# main.net
KiCad netlist of a schematic drawn in Altium Designer
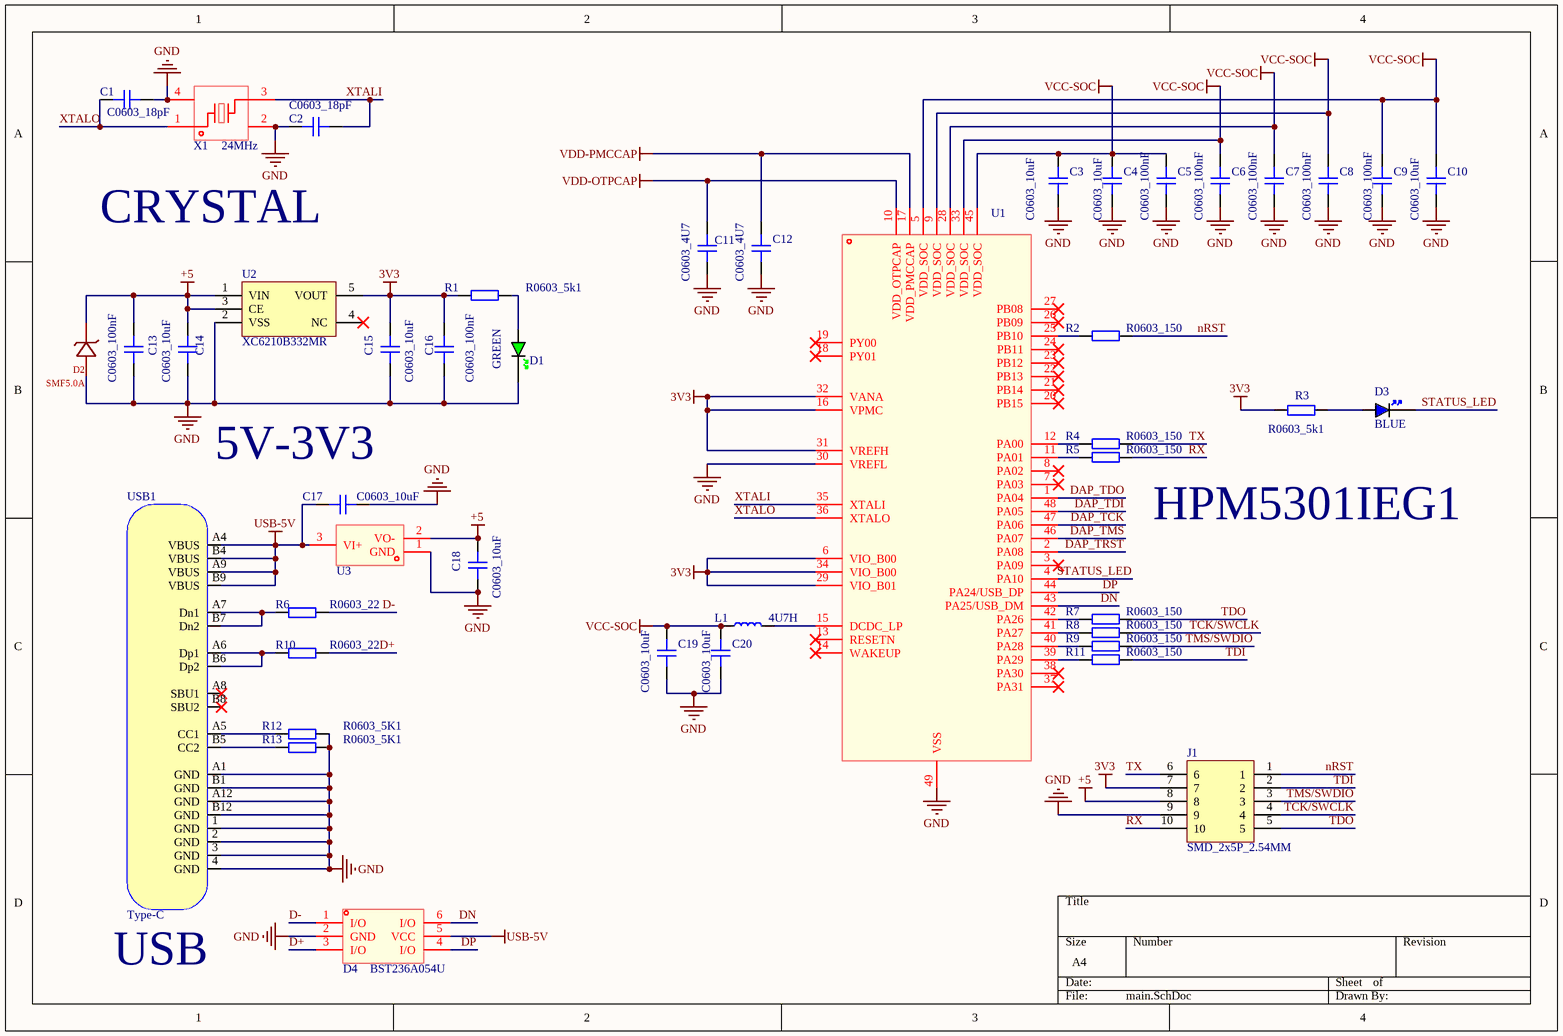
[diagram p0: main.SchDoc]

(export (version "E")
  (design (tool "Eeschema 10.0.6"))
  (components
    (comp (ref "C1")
      (value "C0603_18pF")
      (footprint "CAP_0603")
      (description "Capacitor SMD 0603")
      (libsource (lib "MyLib") (part "CAP_0603"))
    )
    (comp (ref "C2")
      (value "C0603_18pF")
      (footprint "CAP_0603")
      (description "Capacitor SMD 0603")
      (libsource (lib "MyLib") (part "CAP_0603"))
    )
    (comp (ref "C3")
      (value "C0603_10uF")
      (footprint "CAP_0603")
      (description "Capacitor SMD 0603")
      (libsource (lib "MyLib") (part "CAP_0603"))
    )
    (comp (ref "C4")
      (value "C0603_10uF")
      (footprint "CAP_0603")
      (description "Capacitor SMD 0603")
      (libsource (lib "MyLib") (part "CAP_0603"))
    )
    (comp (ref "C5")
      (value "C0603_100nF")
      (footprint "CAP_0603")
      (description "Capacitor SMD 0603")
      (libsource (lib "MyLib") (part "CAP_0603"))
    )
    (comp (ref "C6")
      (value "C0603_100nF")
      (footprint "CAP_0603")
      (description "Capacitor SMD 0603")
      (libsource (lib "MyLib") (part "CAP_0603"))
    )
    (comp (ref "C7")
      (value "C0603_100nF")
      (footprint "CAP_0603")
      (description "Capacitor SMD 0603")
      (libsource (lib "MyLib") (part "CAP_0603"))
    )
    (comp (ref "C8")
      (value "C0603_100nF")
      (footprint "CAP_0603")
      (description "Capacitor SMD 0603")
      (libsource (lib "MyLib") (part "CAP_0603"))
    )
    (comp (ref "C9")
      (value "C0603_100nF")
      (footprint "CAP_0603")
      (description "Capacitor SMD 0603")
      (libsource (lib "MyLib") (part "CAP_0603"))
    )
    (comp (ref "C10")
      (value "C0603_10uF")
      (footprint "CAP_0603")
      (description "Capacitor SMD 0603")
      (libsource (lib "MyLib") (part "CAP_0603"))
    )
    (comp (ref "C11")
      (value "C0603_4U7")
      (footprint "CAP_0603")
      (description "Capacitor SMD 0603")
      (libsource (lib "MyLib") (part "CAP_0603"))
    )
    (comp (ref "C12")
      (value "C0603_4U7")
      (footprint "CAP_0603")
      (description "Capacitor SMD 0603")
      (libsource (lib "MyLib") (part "CAP_0603"))
    )
    (comp (ref "C13")
      (value "C0603_100nF")
      (footprint "CAP_0603")
      (description "Capacitor SMD 0603")
      (libsource (lib "MyLib") (part "CAP_0603"))
    )
    (comp (ref "C14")
      (value "C0603_10uF")
      (footprint "CAP_0603")
      (description "Capacitor SMD 0603")
      (libsource (lib "MyLib") (part "CAP_0603"))
    )
    (comp (ref "C15")
      (value "C0603_10uF")
      (footprint "CAP_0603")
      (description "Capacitor SMD 0603")
      (libsource (lib "MyLib") (part "CAP_0603"))
    )
    (comp (ref "C16")
      (value "C0603_100nF")
      (footprint "CAP_0603")
      (description "Capacitor SMD 0603")
      (libsource (lib "MyLib") (part "CAP_0603"))
    )
    (comp (ref "C17")
      (value "C0603_10uF")
      (footprint "CAP_0603")
      (description "Capacitor SMD 0603")
      (libsource (lib "MyLib") (part "CAP_0603"))
    )
    (comp (ref "C18")
      (value "C0603_10uF")
      (footprint "CAP_0603")
      (description "Capacitor SMD 0603")
      (libsource (lib "MyLib") (part "CAP_0603"))
    )
    (comp (ref "C19")
      (value "C0603_10uF")
      (footprint "CAP_0603")
      (description "Capacitor SMD 0603")
      (libsource (lib "MyLib") (part "CAP_0603"))
    )
    (comp (ref "C20")
      (value "C0603_10uF")
      (footprint "CAP_0603")
      (description "Capacitor SMD 0603")
      (libsource (lib "MyLib") (part "CAP_0603"))
    )
    (comp (ref "D1")
      (value "GREEN")
      (footprint "LED_0805_GREEN")
      (description "LED 0805 GREEN SMD")
      (libsource (lib "MyLib") (part "LED_0805_GREEN"))
    )
    (comp (ref "D2")
      (value "SMF5.0A")
      (footprint "SOD-123FL_L2.7-W1.8-LS3.8-RD")
      (description "极性:单向;反向截止电压(Vrwm):5V;钳位电压:9.2V;峰值脉冲电流(Ipp):21.7A@10/1000us;峰值脉冲功率(Ppp):200W@10/1000us;击穿电压:7V;")
      (fields (field (name "MANUFACTURER") "R+O(宏嘉诚)"))
      (libsource (lib "MyLib") (part "SMF5.0A_C19077497"))
    )
    (comp (ref "D3")
      (value "BLUE")
      (footprint "LED_0805_BLUE")
      (description "LED 0805 BLUE SMD")
      (libsource (lib "MyLib") (part "LED_0805_BLUE"))
    )
    (comp (ref "D4")
      (value "BST236A054U")
      (footprint "SOT-23-6_L2.9-W1.6-P0.95-LS2.9-BL")
      (description "极性:-;反向截止电压(Vrwm):5V;钳位电压:13V;峰值脉冲电流(Ipp):3.5A;峰值脉冲功率(Ppp):45W@8/20us;击穿电压:6V;")
      (fields (field (name "MANUFACTURER") "BORN(伯恩半导体)"))
      (libsource (lib "MyLib") (part "BST236A054U"))
    )
    (comp (ref "J1")
      (value "SMD_2x5P_2.54MM")
      (footprint "SMD_2x5P_2.54MM")
      (libsource (lib "MyLib") (part "SMD_2x5P_2.54MM"))
    )
    (comp (ref "L1")
      (value "4U7H")
      (footprint "IND_1008")
      (description "Inductor SMD 1008")
      (libsource (lib "MyLib") (part "IND_1008"))
    )
    (comp (ref "R1")
      (value "R0603_5k1")
      (footprint "RES_0603")
      (description "Resistor SMD 0603")
      (libsource (lib "MyLib") (part "RES_0603"))
    )
    (comp (ref "R2")
      (value "R0603_150")
      (footprint "RES_0603")
      (description "Resistor SMD 0603")
      (libsource (lib "MyLib") (part "RES_0603"))
    )
    (comp (ref "R3")
      (value "R0603_5k1")
      (footprint "RES_0603")
      (description "Resistor SMD 0603")
      (libsource (lib "MyLib") (part "RES_0603"))
    )
    (comp (ref "R4")
      (value "R0603_150")
      (footprint "RES_0603")
      (description "Resistor SMD 0603")
      (libsource (lib "MyLib") (part "RES_0603"))
    )
    (comp (ref "R5")
      (value "R0603_150")
      (footprint "RES_0603")
      (description "Resistor SMD 0603")
      (libsource (lib "MyLib") (part "RES_0603"))
    )
    (comp (ref "R6")
      (value "R0603_22")
      (footprint "RES_0603")
      (description "Resistor SMD 0603")
      (libsource (lib "MyLib") (part "RES_0603"))
    )
    (comp (ref "R7")
      (value "R0603_150")
      (footprint "RES_0603")
      (description "Resistor SMD 0603")
      (libsource (lib "MyLib") (part "RES_0603"))
    )
    (comp (ref "R8")
      (value "R0603_150")
      (footprint "RES_0603")
      (description "Resistor SMD 0603")
      (libsource (lib "MyLib") (part "RES_0603"))
    )
    (comp (ref "R9")
      (value "R0603_150")
      (footprint "RES_0603")
      (description "Resistor SMD 0603")
      (libsource (lib "MyLib") (part "RES_0603"))
    )
    (comp (ref "R10")
      (value "R0603_22")
      (footprint "RES_0603")
      (description "Resistor SMD 0603")
      (libsource (lib "MyLib") (part "RES_0603"))
    )
    (comp (ref "R11")
      (value "R0603_150")
      (footprint "RES_0603")
      (description "Resistor SMD 0603")
      (libsource (lib "MyLib") (part "RES_0603"))
    )
    (comp (ref "R12")
      (value "R0603_5K1")
      (footprint "RES_0603")
      (description "Resistor SMD 0603")
      (libsource (lib "MyLib") (part "RES_0603"))
    )
    (comp (ref "R13")
      (value "R0603_5K1")
      (footprint "RES_0603")
      (description "Resistor SMD 0603")
      (libsource (lib "MyLib") (part "RES_0603"))
    )
    (comp (ref "U1")
      (value "HPM5301IEG1")
      (footprint "QFN-48_L6.0-W6.0-P0.40-TL-EP4.2")
      (fields (field (name "MANUFACTURER") "HPMICRO(先楫半导体)"))
      (libsource (lib "MyLib") (part "HPM5301IEG1_C49451864"))
    )
    (comp (ref "U2")
      (value "XC6210B332MR")
      (footprint "SOT-23-5")
      (description "LDO 3V3@700mA")
      (libsource (lib "MyLib") (part "XC6210B332MR"))
    )
    (comp (ref "U3")
      (value "CH213K")
      (footprint "SOT-23-3_L2.9-W1.6-P1.90-LS2.8-BR")
      (fields (field (name "MANUFACTURER") "WCH(南京沁恒)"))
      (libsource (lib "CHIPS") (part "CH213K"))
    )
    (comp (ref "USB1")
      (value "Type-C")
      (footprint "TYPE-C_16P")
      (description "USB-Type-C_16P")
      (libsource (lib "MyLib") (part "USB-Type-C"))
    )
    (comp (ref "X1")
      (value "24MHz")
      (footprint "CRYSTAL-SMD_4P-L2.5-W2.0-BL-A")
      (description "晶振类型:贴片晶振;频率:24MHz;常温频差:±10ppm;负载电容:18pF;频率稳定度:±10ppm;")
      (fields
        (field (name "MANUFACTURER") "HCI(杭晶)")
        (field (name "MANUFACTURER PART") "XC22M4-32.000-F08NNHP")
      )
      (libsource (lib "MyLib") (part "XTAL_2520_24MHz"))
    )
  )
  (nets
    (net (code "1") (name "+5") (class "Default")
      (node (ref "C13") (pin "1") (pinfunction "1_1") (pintype "passive"))
      (node (ref "C14") (pin "2") (pinfunction "2_2") (pintype "passive"))
      (node (ref "C18") (pin "2") (pinfunction "2_2") (pintype "passive"))
      (node (ref "D2") (pin "1") (pinfunction "K_1") (pintype "passive"))
      (node (ref "J1") (pin "8") (pinfunction "8_8") (pintype "passive"))
      (node (ref "U2") (pin "1") (pinfunction "VIN_1") (pintype "passive"))
      (node (ref "U2") (pin "3") (pinfunction "CE_3") (pintype "passive"))
      (node (ref "U3") (pin "2") (pinfunction "VO-_2") (pintype "passive"))
    )
    (net (code "2") (name "/D+") (class "Default")
      (node (ref "D4") (pin "3") (pinfunction "I/O_3") (pintype "passive"))
      (node (ref "R10") (pin "2") (pinfunction "2_2") (pintype "passive"))
    )
    (net (code "3") (name "/D-") (class "Default")
      (node (ref "D4") (pin "1") (pinfunction "I/O_1") (pintype "passive"))
      (node (ref "R6") (pin "2") (pinfunction "2_2") (pintype "passive"))
    )
    (net (code "4") (name "/DAP_TCK") (class "Default")
      (node (ref "U1") (pin "47") (pinfunction "PA06_47") (pintype "passive"))
    )
    (net (code "5") (name "/DAP_TDI") (class "Default")
      (node (ref "U1") (pin "48") (pinfunction "PA05_48") (pintype "passive"))
    )
    (net (code "6") (name "/DAP_TDO") (class "Default")
      (node (ref "U1") (pin "1") (pinfunction "PA04_1") (pintype "passive"))
    )
    (net (code "7") (name "/DAP_TMS") (class "Default")
      (node (ref "U1") (pin "46") (pinfunction "PA07_46") (pintype "passive"))
    )
    (net (code "8") (name "/DAP_TRST") (class "Default")
      (node (ref "U1") (pin "2") (pinfunction "PA08_2") (pintype "passive"))
    )
    (net (code "9") (name "/DN") (class "Default")
      (node (ref "D4") (pin "6") (pinfunction "I/O_6") (pintype "passive"))
      (node (ref "U1") (pin "43") (pinfunction "PA25/USB_DM_43") (pintype "passive"))
    )
    (net (code "10") (name "/DP") (class "Default")
      (node (ref "D4") (pin "4") (pinfunction "I/O_4") (pintype "passive"))
      (node (ref "U1") (pin "44") (pinfunction "PA24/USB_DP_44") (pintype "passive"))
    )
    (net (code "11") (name "/RX") (class "Default")
      (node (ref "J1") (pin "10") (pinfunction "10_10") (pintype "passive"))
      (node (ref "R5") (pin "2") (pinfunction "2_2") (pintype "passive"))
    )
    (net (code "12") (name "/STATUS_LED") (class "Default")
      (node (ref "D3") (pin "K") (pinfunction "K_K") (pintype "passive"))
      (node (ref "U1") (pin "4") (pinfunction "PA10_4") (pintype "passive"))
    )
    (net (code "13") (name "/TCK{slash}SWCLK") (class "Default")
      (node (ref "J1") (pin "4") (pinfunction "4_4") (pintype "passive"))
      (node (ref "R8") (pin "2") (pinfunction "2_2") (pintype "passive"))
    )
    (net (code "14") (name "/TDI") (class "Default")
      (node (ref "J1") (pin "2") (pinfunction "2_2") (pintype "passive"))
      (node (ref "R11") (pin "2") (pinfunction "2_2") (pintype "passive"))
    )
    (net (code "15") (name "/TDO") (class "Default")
      (node (ref "J1") (pin "5") (pinfunction "5_5") (pintype "passive"))
      (node (ref "R7") (pin "2") (pinfunction "2_2") (pintype "passive"))
    )
    (net (code "16") (name "/TMS{slash}SWDIO") (class "Default")
      (node (ref "J1") (pin "3") (pinfunction "3_3") (pintype "passive"))
      (node (ref "R9") (pin "2") (pinfunction "2_2") (pintype "passive"))
    )
    (net (code "17") (name "/TX") (class "Default")
      (node (ref "J1") (pin "6") (pinfunction "6_6") (pintype "passive"))
      (node (ref "R4") (pin "2") (pinfunction "2_2") (pintype "passive"))
    )
    (net (code "18") (name "/XTALI") (class "Default")
      (node (ref "C2") (pin "1") (pinfunction "1_1") (pintype "passive"))
      (node (ref "U1") (pin "35") (pinfunction "XTALI_35") (pintype "passive"))
      (node (ref "X1") (pin "3") (pinfunction "3_3") (pintype "passive"))
    )
    (net (code "19") (name "/XTALO") (class "Default")
      (node (ref "C1") (pin "2") (pinfunction "2_2") (pintype "passive"))
      (node (ref "U1") (pin "36") (pinfunction "XTALO_36") (pintype "passive"))
      (node (ref "X1") (pin "1") (pinfunction "1_1") (pintype "passive"))
    )
    (net (code "20") (name "/nRST") (class "Default")
      (node (ref "J1") (pin "1") (pinfunction "1_1") (pintype "passive"))
      (node (ref "R2") (pin "2") (pinfunction "2_2") (pintype "passive"))
    )
    (net (code "21") (name "3V3") (class "Default")
      (node (ref "C15") (pin "2") (pinfunction "2_2") (pintype "passive"))
      (node (ref "C16") (pin "2") (pinfunction "2_2") (pintype "passive"))
      (node (ref "J1") (pin "7") (pinfunction "7_7") (pintype "passive"))
      (node (ref "R1") (pin "1") (pinfunction "1_1") (pintype "passive"))
      (node (ref "R3") (pin "1") (pinfunction "1_1") (pintype "passive"))
      (node (ref "U1") (pin "16") (pinfunction "VPMC_16") (pintype "passive"))
      (node (ref "U1") (pin "29") (pinfunction "VIO_B01_29") (pintype "passive"))
      (node (ref "U1") (pin "31") (pinfunction "VREFH_31") (pintype "passive"))
      (node (ref "U1") (pin "32") (pinfunction "VANA_32") (pintype "passive"))
      (node (ref "U1") (pin "34") (pinfunction "VIO_B00_34") (pintype "passive"))
      (node (ref "U1") (pin "6") (pinfunction "VIO_B00_6") (pintype "passive"))
      (node (ref "U2") (pin "5") (pinfunction "VOUT_5") (pintype "passive"))
    )
    (net (code "22") (name "GND") (class "Default")
      (node (ref "C1") (pin "1") (pinfunction "1_1") (pintype "passive"))
      (node (ref "C10") (pin "1") (pinfunction "1_1") (pintype "passive"))
      (node (ref "C11") (pin "1") (pinfunction "1_1") (pintype "passive"))
      (node (ref "C12") (pin "1") (pinfunction "1_1") (pintype "passive"))
      (node (ref "C13") (pin "2") (pinfunction "2_2") (pintype "passive"))
      (node (ref "C14") (pin "1") (pinfunction "1_1") (pintype "passive"))
      (node (ref "C15") (pin "1") (pinfunction "1_1") (pintype "passive"))
      (node (ref "C16") (pin "1") (pinfunction "1_1") (pintype "passive"))
      (node (ref "C17") (pin "1") (pinfunction "1_1") (pintype "passive"))
      (node (ref "C18") (pin "1") (pinfunction "1_1") (pintype "passive"))
      (node (ref "C19") (pin "1") (pinfunction "1_1") (pintype "passive"))
      (node (ref "C2") (pin "2") (pinfunction "2_2") (pintype "passive"))
      (node (ref "C20") (pin "1") (pinfunction "1_1") (pintype "passive"))
      (node (ref "C3") (pin "1") (pinfunction "1_1") (pintype "passive"))
      (node (ref "C4") (pin "1") (pinfunction "1_1") (pintype "passive"))
      (node (ref "C5") (pin "1") (pinfunction "1_1") (pintype "passive"))
      (node (ref "C6") (pin "1") (pinfunction "1_1") (pintype "passive"))
      (node (ref "C7") (pin "1") (pinfunction "1_1") (pintype "passive"))
      (node (ref "C8") (pin "1") (pinfunction "1_1") (pintype "passive"))
      (node (ref "C9") (pin "1") (pinfunction "1_1") (pintype "passive"))
      (node (ref "D1") (pin "K") (pinfunction "K_K") (pintype "passive"))
      (node (ref "D2") (pin "2") (pinfunction "A_2") (pintype "passive"))
      (node (ref "D4") (pin "2") (pinfunction "GND_2") (pintype "passive"))
      (node (ref "J1") (pin "9") (pinfunction "9_9") (pintype "passive"))
      (node (ref "R12") (pin "2") (pinfunction "2_2") (pintype "passive"))
      (node (ref "R13") (pin "2") (pinfunction "2_2") (pintype "passive"))
      (node (ref "U1") (pin "30") (pinfunction "VREFL_30") (pintype "passive"))
      (node (ref "U1") (pin "49") (pinfunction "VSS_49") (pintype "passive"))
      (node (ref "U2") (pin "2") (pinfunction "VSS_2") (pintype "passive"))
      (node (ref "U3") (pin "1") (pinfunction "GND_1") (pintype "passive"))
      (node (ref "USB1") (pin "1") (pinfunction "GND_1") (pintype "passive"))
      (node (ref "USB1") (pin "2") (pinfunction "GND_2") (pintype "passive"))
      (node (ref "USB1") (pin "3") (pinfunction "GND_3") (pintype "passive"))
      (node (ref "USB1") (pin "4") (pinfunction "GND_4") (pintype "passive"))
      (node (ref "USB1") (pin "A1") (pinfunction "GND_A1") (pintype "passive"))
      (node (ref "USB1") (pin "A12") (pinfunction "GND_A12") (pintype "passive"))
      (node (ref "USB1") (pin "B1") (pinfunction "GND_B1") (pintype "passive"))
      (node (ref "USB1") (pin "B12") (pinfunction "GND_B12") (pintype "passive"))
      (node (ref "X1") (pin "2") (pinfunction "GND_2") (pintype "passive"))
      (node (ref "X1") (pin "4") (pinfunction "GND_4") (pintype "passive"))
    )
    (net (code "23") (name "Net-(D1-PadA)") (class "Default")
      (node (ref "D1") (pin "A") (pinfunction "A_A") (pintype "passive"))
      (node (ref "R1") (pin "2") (pinfunction "2_2") (pintype "passive"))
    )
    (net (code "24") (name "Net-(D3-PadA)") (class "Default")
      (node (ref "D3") (pin "A") (pinfunction "A_A") (pintype "passive"))
      (node (ref "R3") (pin "2") (pinfunction "2_2") (pintype "passive"))
    )
    (net (code "25") (name "Net-(U1-DCDC_LP)") (class "Default")
      (node (ref "L1") (pin "2") (pinfunction "2_2") (pintype "passive"))
      (node (ref "U1") (pin "15") (pinfunction "DCDC_LP_15") (pintype "passive"))
    )
    (net (code "26") (name "Net-(U1-PA00)") (class "Default")
      (node (ref "R4") (pin "1") (pinfunction "1_1") (pintype "passive"))
      (node (ref "U1") (pin "12") (pinfunction "PA00_12") (pintype "passive"))
    )
    (net (code "27") (name "Net-(U1-PA01)") (class "Default")
      (node (ref "R5") (pin "1") (pinfunction "1_1") (pintype "passive"))
      (node (ref "U1") (pin "11") (pinfunction "PA01_11") (pintype "passive"))
    )
    (net (code "28") (name "Net-(U1-PA26)") (class "Default")
      (node (ref "R7") (pin "1") (pinfunction "1_1") (pintype "passive"))
      (node (ref "U1") (pin "42") (pinfunction "PA26_42") (pintype "passive"))
    )
    (net (code "29") (name "Net-(U1-PA27)") (class "Default")
      (node (ref "R8") (pin "1") (pinfunction "1_1") (pintype "passive"))
      (node (ref "U1") (pin "41") (pinfunction "PA27_41") (pintype "passive"))
    )
    (net (code "30") (name "Net-(U1-PA28)") (class "Default")
      (node (ref "R9") (pin "1") (pinfunction "1_1") (pintype "passive"))
      (node (ref "U1") (pin "40") (pinfunction "PA28_40") (pintype "passive"))
    )
    (net (code "31") (name "Net-(U1-PA29)") (class "Default")
      (node (ref "R11") (pin "1") (pinfunction "1_1") (pintype "passive"))
      (node (ref "U1") (pin "39") (pinfunction "PA29_39") (pintype "passive"))
    )
    (net (code "32") (name "Net-(U1-PB10)") (class "Default")
      (node (ref "R2") (pin "1") (pinfunction "1_1") (pintype "passive"))
      (node (ref "U1") (pin "25") (pinfunction "PB10_25") (pintype "passive"))
    )
    (net (code "33") (name "Net-(USB1-CC1)") (class "Default")
      (node (ref "R12") (pin "1") (pinfunction "1_1") (pintype "passive"))
      (node (ref "USB1") (pin "A5") (pinfunction "CC1_A5") (pintype "passive"))
    )
    (net (code "34") (name "Net-(USB1-CC2)") (class "Default")
      (node (ref "R13") (pin "1") (pinfunction "1_1") (pintype "passive"))
      (node (ref "USB1") (pin "B5") (pinfunction "CC2_B5") (pintype "passive"))
    )
    (net (code "35") (name "Net-(USB1-Dn1)") (class "Default")
      (node (ref "R6") (pin "1") (pinfunction "1_1") (pintype "passive"))
      (node (ref "USB1") (pin "A7") (pinfunction "Dn1_A7") (pintype "passive"))
      (node (ref "USB1") (pin "B7") (pinfunction "Dn2_B7") (pintype "passive"))
    )
    (net (code "36") (name "Net-(USB1-Dp1)") (class "Default")
      (node (ref "R10") (pin "1") (pinfunction "1_1") (pintype "passive"))
      (node (ref "USB1") (pin "A6") (pinfunction "Dp1_A6") (pintype "passive"))
      (node (ref "USB1") (pin "B6") (pinfunction "Dp2_B6") (pintype "passive"))
    )
    (net (code "37") (name "USB-5V") (class "Default")
      (node (ref "C17") (pin "2") (pinfunction "2_2") (pintype "passive"))
      (node (ref "D4") (pin "5") (pinfunction "VCC_5") (pintype "passive"))
      (node (ref "U3") (pin "3") (pinfunction "VI+_3") (pintype "passive"))
      (node (ref "USB1") (pin "A4") (pinfunction "VBUS_A4") (pintype "passive"))
      (node (ref "USB1") (pin "A9") (pinfunction "VBUS_A9") (pintype "passive"))
      (node (ref "USB1") (pin "B4") (pinfunction "VBUS_B4") (pintype "passive"))
      (node (ref "USB1") (pin "B9") (pinfunction "VBUS_B9") (pintype "passive"))
    )
    (net (code "38") (name "VCC-SOC") (class "Default")
      (node (ref "C10") (pin "2") (pinfunction "2_2") (pintype "passive"))
      (node (ref "C19") (pin "2") (pinfunction "2_2") (pintype "passive"))
      (node (ref "C20") (pin "2") (pinfunction "2_2") (pintype "passive"))
      (node (ref "C3") (pin "2") (pinfunction "2_2") (pintype "passive"))
      (node (ref "C4") (pin "2") (pinfunction "2_2") (pintype "passive"))
      (node (ref "C5") (pin "2") (pinfunction "2_2") (pintype "passive"))
      (node (ref "C6") (pin "2") (pinfunction "2_2") (pintype "passive"))
      (node (ref "C7") (pin "2") (pinfunction "2_2") (pintype "passive"))
      (node (ref "C8") (pin "2") (pinfunction "2_2") (pintype "passive"))
      (node (ref "C9") (pin "2") (pinfunction "2_2") (pintype "passive"))
      (node (ref "L1") (pin "1") (pinfunction "1_1") (pintype "passive"))
      (node (ref "U1") (pin "28") (pinfunction "VDD_SOC_28") (pintype "passive"))
      (node (ref "U1") (pin "33") (pinfunction "VDD_SOC_33") (pintype "passive"))
      (node (ref "U1") (pin "45") (pinfunction "VDD_SOC_45") (pintype "passive"))
      (node (ref "U1") (pin "5") (pinfunction "VDD_SOC_5") (pintype "passive"))
      (node (ref "U1") (pin "9") (pinfunction "VDD_SOC_9") (pintype "passive"))
    )
    (net (code "39") (name "VDD-OTPCAP") (class "Default")
      (node (ref "C11") (pin "2") (pinfunction "2_2") (pintype "passive"))
      (node (ref "U1") (pin "10") (pinfunction "VDD_OTPCAP_10") (pintype "passive"))
    )
    (net (code "40") (name "VDD-PMCCAP") (class "Default")
      (node (ref "C12") (pin "2") (pinfunction "2_2") (pintype "passive"))
      (node (ref "U1") (pin "17") (pinfunction "VDD_PMCCAP_17") (pintype "passive"))
    )
    (net (code "41") (name "unconnected-(U1-PA02-Pad8)") (class "Default")
      (node (ref "U1") (pin "8") (pinfunction "PA02_8") (pintype "passive+no_connect"))
    )
    (net (code "42") (name "unconnected-(U1-PA03-Pad7)") (class "Default")
      (node (ref "U1") (pin "7") (pinfunction "PA03_7") (pintype "passive+no_connect"))
    )
    (net (code "43") (name "unconnected-(U1-PA09-Pad3)") (class "Default")
      (node (ref "U1") (pin "3") (pinfunction "PA09_3") (pintype "passive+no_connect"))
    )
    (net (code "44") (name "unconnected-(U1-PA30-Pad38)") (class "Default")
      (node (ref "U1") (pin "38") (pinfunction "PA30_38") (pintype "passive+no_connect"))
    )
    (net (code "45") (name "unconnected-(U1-PA31-Pad37)") (class "Default")
      (node (ref "U1") (pin "37") (pinfunction "PA31_37") (pintype "passive+no_connect"))
    )
    (net (code "46") (name "unconnected-(U1-PB08-Pad27)") (class "Default")
      (node (ref "U1") (pin "27") (pinfunction "PB08_27") (pintype "passive+no_connect"))
    )
    (net (code "47") (name "unconnected-(U1-PB09-Pad26)") (class "Default")
      (node (ref "U1") (pin "26") (pinfunction "PB09_26") (pintype "passive+no_connect"))
    )
    (net (code "48") (name "unconnected-(U1-PB11-Pad24)") (class "Default")
      (node (ref "U1") (pin "24") (pinfunction "PB11_24") (pintype "passive+no_connect"))
    )
    (net (code "49") (name "unconnected-(U1-PB12-Pad23)") (class "Default")
      (node (ref "U1") (pin "23") (pinfunction "PB12_23") (pintype "passive+no_connect"))
    )
    (net (code "50") (name "unconnected-(U1-PB13-Pad22)") (class "Default")
      (node (ref "U1") (pin "22") (pinfunction "PB13_22") (pintype "passive+no_connect"))
    )
    (net (code "51") (name "unconnected-(U1-PB14-Pad21)") (class "Default")
      (node (ref "U1") (pin "21") (pinfunction "PB14_21") (pintype "passive+no_connect"))
    )
    (net (code "52") (name "unconnected-(U1-PB15-Pad20)") (class "Default")
      (node (ref "U1") (pin "20") (pinfunction "PB15_20") (pintype "passive+no_connect"))
    )
    (net (code "53") (name "unconnected-(U1-PY00-Pad19)") (class "Default")
      (node (ref "U1") (pin "19") (pinfunction "PY00_19") (pintype "passive+no_connect"))
    )
    (net (code "54") (name "unconnected-(U1-PY01-Pad18)") (class "Default")
      (node (ref "U1") (pin "18") (pinfunction "PY01_18") (pintype "passive+no_connect"))
    )
    (net (code "55") (name "unconnected-(U1-RESETN-Pad13)") (class "Default")
      (node (ref "U1") (pin "13") (pinfunction "RESETN_13") (pintype "passive+no_connect"))
    )
    (net (code "56") (name "unconnected-(U1-WAKEUP-Pad14)") (class "Default")
      (node (ref "U1") (pin "14") (pinfunction "WAKEUP_14") (pintype "passive+no_connect"))
    )
    (net (code "57") (name "unconnected-(U2-NC-Pad4)") (class "Default")
      (node (ref "U2") (pin "4") (pinfunction "NC_4") (pintype "passive+no_connect"))
    )
    (net (code "58") (name "unconnected-(USB1-SBU1-PadA8)") (class "Default")
      (node (ref "USB1") (pin "A8") (pinfunction "SBU1_A8") (pintype "passive+no_connect"))
    )
    (net (code "59") (name "unconnected-(USB1-SBU2-PadB8)") (class "Default")
      (node (ref "USB1") (pin "B8") (pinfunction "SBU2_B8") (pintype "passive+no_connect"))
    )
  )
)
